# power_electronics2.net
KiCad netlist of a schematic drawn in EAGLE
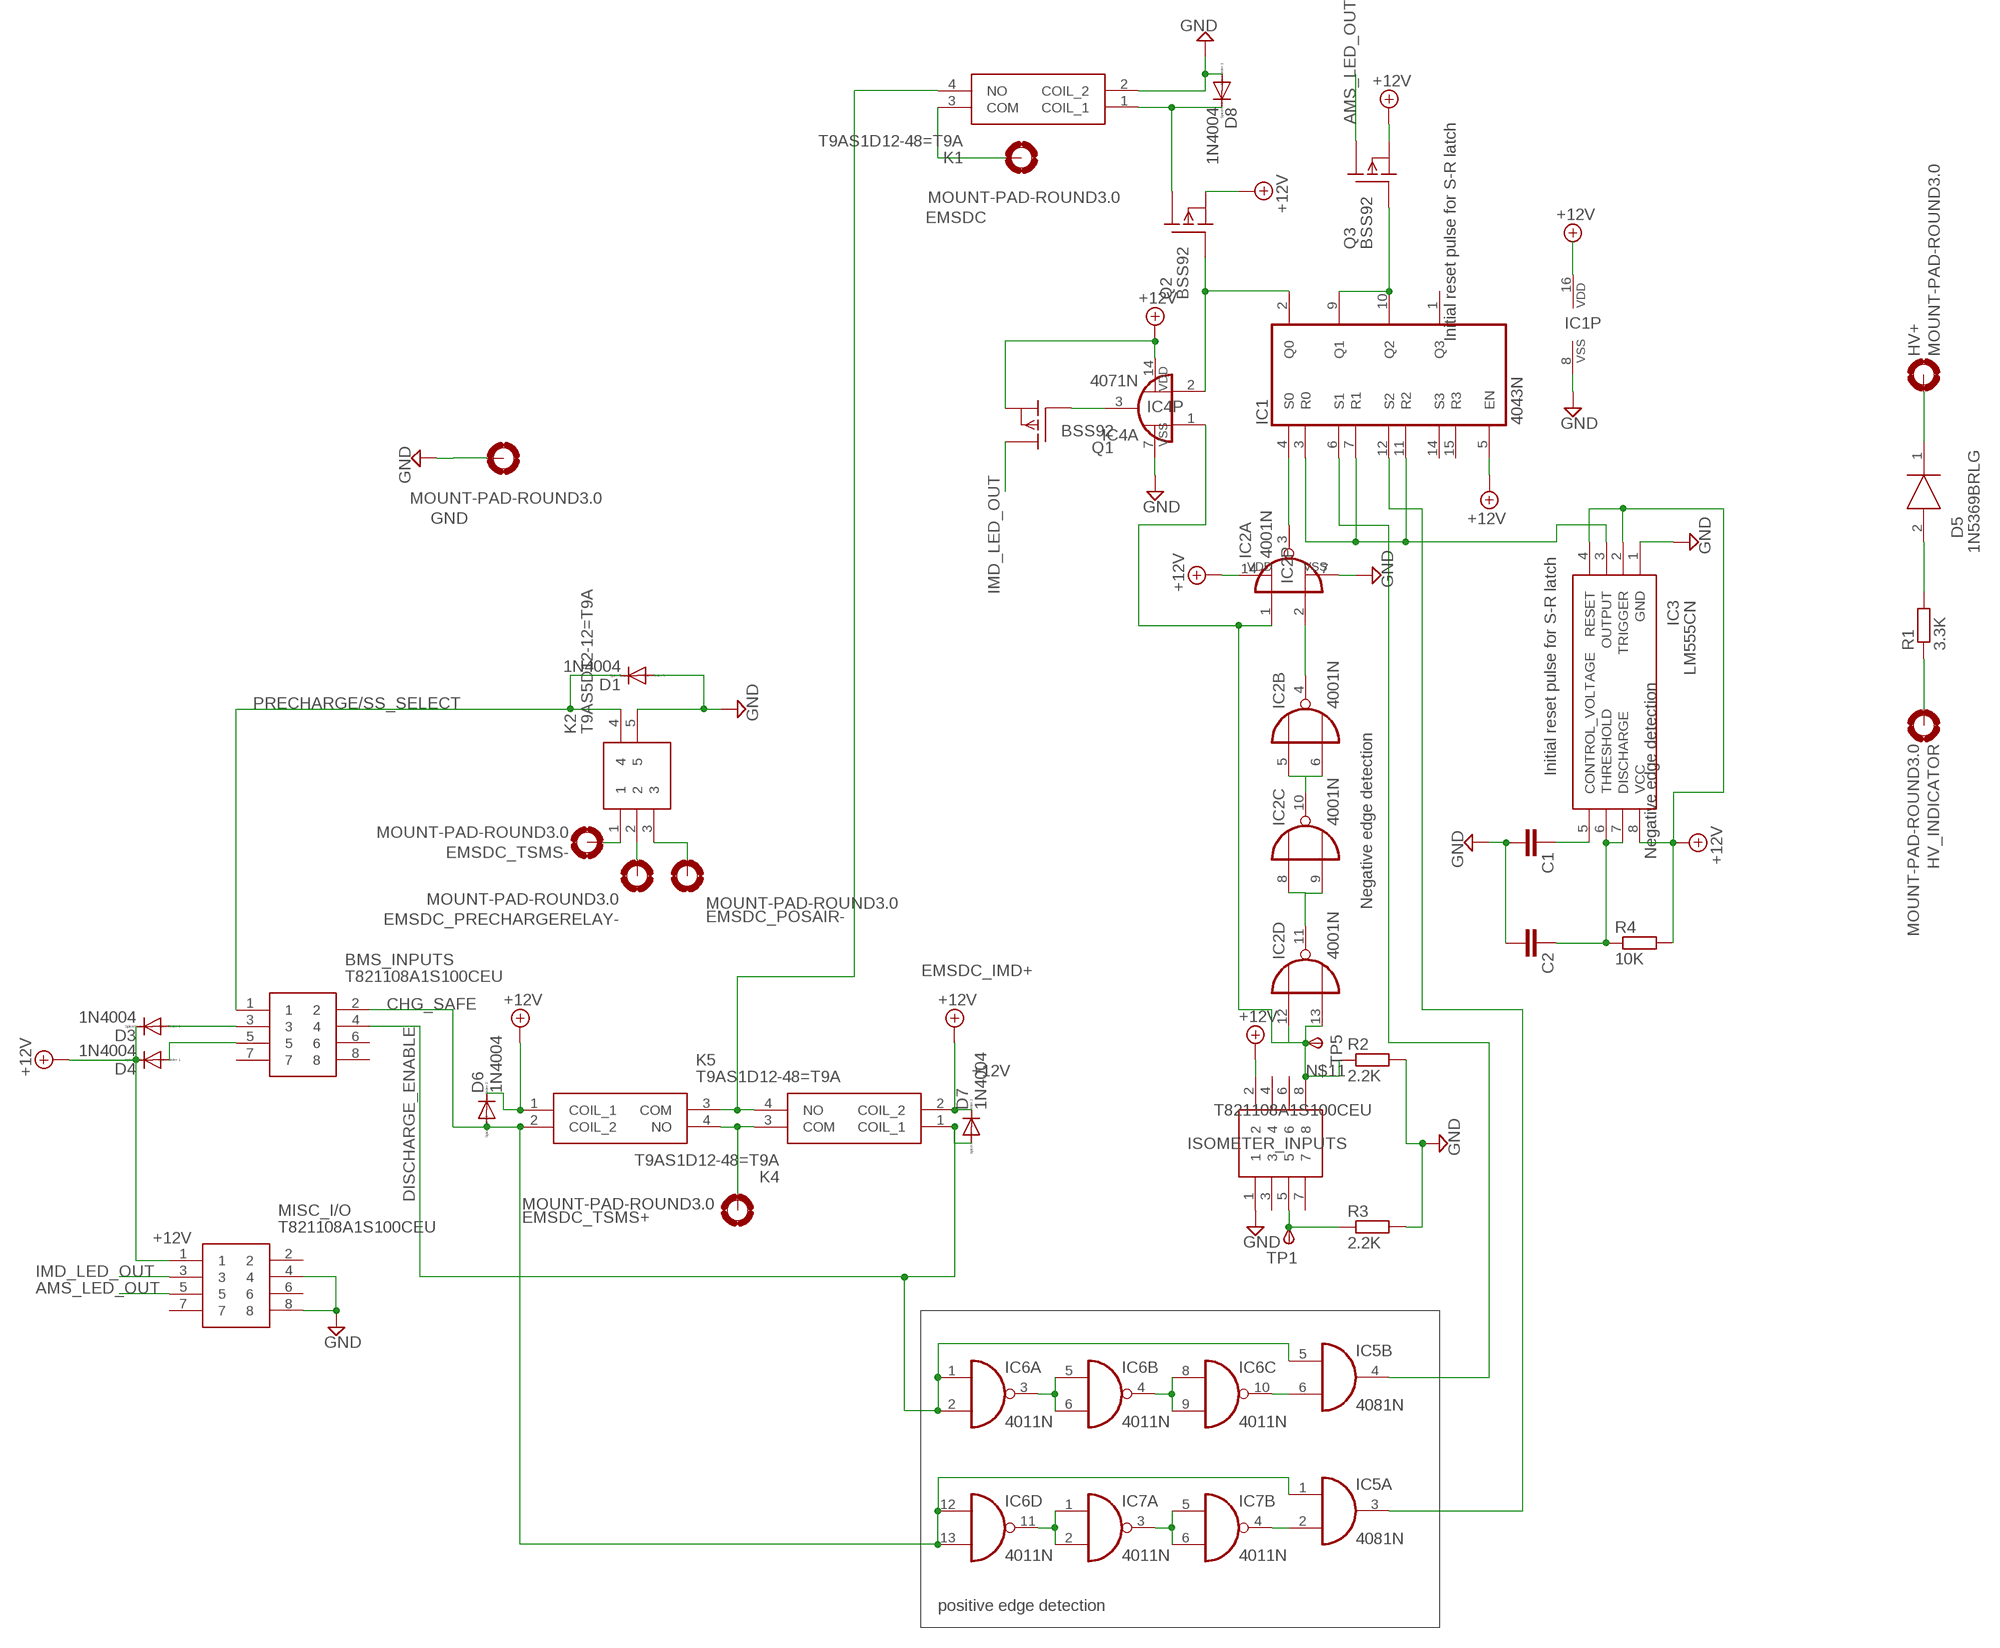
[diagram p0: schematic, sheet 1]

(export (version "E")
  (design (tool "Eeschema 10.0.6"))
  (components
    (comp (ref "BMS_INPUTS")
      (value "T821108A1S100CEU")
      (footprint "eagle-import:HDRV8W64P254_2X4_1778X895X915P")
      (fields (field (name "RS_PART_NUMBER") "8323569"))
      (libsource (lib "eagle-import") (part "T821108A1S100CEU"))
    )
    (comp (ref "C1")
      (value "C-EU050-024X044")
      (footprint "eagle-import:C050-024X044")
      (libsource (lib "eagle-import") (part "C-EU050-024X044"))
    )
    (comp (ref "C2")
      (value "C-EU050-024X044")
      (footprint "eagle-import:C050-024X044")
      (libsource (lib "eagle-import") (part "C-EU050-024X044"))
    )
    (comp (ref "D1")
      (value "1N4004")
      (footprint "eagle-import:DO41-10")
      (libsource (lib "eagle-import") (part "1N4004"))
    )
    (comp (ref "D3")
      (value "1N4004")
      (footprint "eagle-import:DO41-10")
      (libsource (lib "eagle-import") (part "1N4004"))
    )
    (comp (ref "D4")
      (value "1N4004")
      (footprint "eagle-import:DO41-10")
      (libsource (lib "eagle-import") (part "1N4004"))
    )
    (comp (ref "D5")
      (value "1N5369BRLG")
      (footprint "eagle-import:DIOAD2260W109L864D349")
      (fields (field (name "RS_PART_NUMBER") "6547678P"))
      (libsource (lib "eagle-import") (part "1N5369BRLG"))
    )
    (comp (ref "D6")
      (value "1N4004")
      (footprint "eagle-import:DO41-10")
      (libsource (lib "eagle-import") (part "1N4004"))
    )
    (comp (ref "D7")
      (value "1N4004")
      (footprint "eagle-import:DO41-10")
      (libsource (lib "eagle-import") (part "1N4004"))
    )
    (comp (ref "D8")
      (value "1N4004")
      (footprint "eagle-import:DO41-10")
      (libsource (lib "eagle-import") (part "1N4004"))
    )
    (comp (ref "EMSDC")
      (value "MOUNT-PAD-ROUND3.0")
      (footprint "eagle-import:3,0-PAD")
      (libsource (lib "eagle-import") (part "MOUNT-PAD-ROUND3.0"))
    )
    (comp (ref "EMSDC_POSAIR-")
      (value "MOUNT-PAD-ROUND3.0")
      (footprint "eagle-import:3,0-PAD")
      (libsource (lib "eagle-import") (part "MOUNT-PAD-ROUND3.0"))
    )
    (comp (ref "EMSDC_PRECHARGERELAY-")
      (value "MOUNT-PAD-ROUND3.0")
      (footprint "eagle-import:3,0-PAD")
      (libsource (lib "eagle-import") (part "MOUNT-PAD-ROUND3.0"))
    )
    (comp (ref "EMSDC_TSMS+")
      (value "MOUNT-PAD-ROUND3.0")
      (footprint "eagle-import:3,0-PAD")
      (libsource (lib "eagle-import") (part "MOUNT-PAD-ROUND3.0"))
    )
    (comp (ref "EMSDC_TSMS-")
      (value "MOUNT-PAD-ROUND3.0")
      (footprint "eagle-import:3,0-PAD")
      (libsource (lib "eagle-import") (part "MOUNT-PAD-ROUND3.0"))
    )
    (comp (ref "GND")
      (value "MOUNT-PAD-ROUND3.0")
      (footprint "eagle-import:3,0-PAD")
      (libsource (lib "eagle-import") (part "MOUNT-PAD-ROUND3.0"))
    )
    (comp (ref "HV+")
      (value "MOUNT-PAD-ROUND3.0")
      (footprint "eagle-import:3,0-PAD")
      (libsource (lib "eagle-import") (part "MOUNT-PAD-ROUND3.0"))
    )
    (comp (ref "HV_INDICATOR")
      (value "MOUNT-PAD-ROUND3.0")
      (footprint "eagle-import:3,0-PAD")
      (libsource (lib "eagle-import") (part "MOUNT-PAD-ROUND3.0"))
    )
    (comp (ref "IC1")
      (value "4043N")
      (footprint "eagle-import:DIL16")
      (libsource (lib "eagle-import") (part "4043N"))
    )
    (comp (ref "IC2")
      (value "4001N")
      (footprint "eagle-import:DIL14")
      (libsource (lib "eagle-import") (part "4001N"))
    )
    (comp (ref "IC3")
      (value "LM555CN")
      (footprint "eagle-import:DIP762W53P254L980H533Q8N")
      (fields (field (name "MOUSER_PART_NUMBER") "512-LM555CN"))
      (libsource (lib "eagle-import") (part "LM555CN"))
    )
    (comp (ref "IC4")
      (value "4071N")
      (footprint "eagle-import:DIL14")
      (libsource (lib "eagle-import") (part "4071N"))
    )
    (comp (ref "IC5")
      (value "4081N")
      (footprint "eagle-import:DIL14")
      (libsource (lib "eagle-import") (part "4081N"))
    )
    (comp (ref "IC6")
      (value "4011N")
      (footprint "eagle-import:DIL14")
      (libsource (lib "eagle-import") (part "4011N"))
    )
    (comp (ref "IC7")
      (value "4011N")
      (footprint "eagle-import:DIL14")
      (libsource (lib "eagle-import") (part "4011N"))
    )
    (comp (ref "ISOMETER_INPUTS")
      (value "T821108A1S100CEU")
      (footprint "eagle-import:HDRV8W64P254_2X4_1778X895X915P")
      (fields (field (name "RS_PART_NUMBER") "8323569"))
      (libsource (lib "eagle-import") (part "T821108A1S100CEU"))
    )
    (comp (ref "K1")
      (value "T9AS1D12-48=T9A")
      (footprint "eagle-import:T9AS1D1248T9A")
      (fields (field (name "RS_PART_NUMBER") "6802534P"))
      (libsource (lib "eagle-import") (part "T9AS1D12-48=T9A"))
    )
    (comp (ref "K2")
      (value "T9AS5D12-12=T9A")
      (footprint "eagle-import:T9AS1D12")
      (fields (field (name "RS_PART_NUMBER") "6802528"))
      (libsource (lib "eagle-import") (part "T9AS5D12-12=T9A"))
    )
    (comp (ref "K4")
      (value "T9AS1D12-48=T9A")
      (footprint "eagle-import:T9AS1D1248T9A")
      (fields (field (name "RS_PART_NUMBER") "6802534P"))
      (libsource (lib "eagle-import") (part "T9AS1D12-48=T9A"))
    )
    (comp (ref "K5")
      (value "T9AS1D12-48=T9A")
      (footprint "eagle-import:T9AS1D1248T9A")
      (fields (field (name "RS_PART_NUMBER") "6802534P"))
      (libsource (lib "eagle-import") (part "T9AS1D12-48=T9A"))
    )
    (comp (ref "MISC_I/O")
      (value "T821108A1S100CEU")
      (footprint "eagle-import:HDRV8W64P254_2X4_1778X895X915P")
      (fields (field (name "RS_PART_NUMBER") "8323569"))
      (libsource (lib "eagle-import") (part "T821108A1S100CEU"))
    )
    (comp (ref "Q1")
      (value "BSS92")
      (footprint "eagle-import:TO92")
      (libsource (lib "eagle-import") (part "BSS92"))
    )
    (comp (ref "Q2")
      (value "BSS92")
      (footprint "eagle-import:TO92")
      (libsource (lib "eagle-import") (part "BSS92"))
    )
    (comp (ref "Q3")
      (value "BSS92")
      (footprint "eagle-import:TO92")
      (libsource (lib "eagle-import") (part "BSS92"))
    )
    (comp (ref "R1")
      (value "3.3K")
      (footprint "eagle-import:0207_15")
      (libsource (lib "eagle-import") (part "R-EU_0207/15"))
    )
    (comp (ref "R2")
      (value "2.2K")
      (footprint "eagle-import:0207_12")
      (libsource (lib "eagle-import") (part "R-EU_0207/12"))
    )
    (comp (ref "R3")
      (value "2.2K")
      (footprint "eagle-import:0207_12")
      (libsource (lib "eagle-import") (part "R-EU_0207/12"))
    )
    (comp (ref "R4")
      (value "10K")
      (footprint "eagle-import:0207_15")
      (libsource (lib "eagle-import") (part "R-EU_0207/15"))
    )
    (comp (ref "TP1")
      (value "TPSPAD1-17")
      (footprint "eagle-import:P1-17")
      (libsource (lib "eagle-import") (part "TPSPAD1-17"))
    )
    (comp (ref "TP5")
      (value "TPSPAD1-17")
      (footprint "eagle-import:P1-17")
      (libsource (lib "eagle-import") (part "TPSPAD1-17"))
    )
  )
  (nets
    (net (code "1") (name "+12V") (class "Default")
      (node (ref "D3") (pin "C") (pinfunction "C_C") (pintype "passive"))
      (node (ref "D4") (pin "C") (pinfunction "C_C") (pintype "passive"))
      (node (ref "D6") (pin "C") (pinfunction "C_C") (pintype "passive"))
      (node (ref "D7") (pin "C") (pinfunction "C_C") (pintype "passive"))
      (node (ref "IC1") (pin "16") (pinfunction "VDD_16") (pintype "power_in"))
      (node (ref "IC1") (pin "5") (pinfunction "EN_5") (pintype "input"))
      (node (ref "IC2") (pin "14") (pinfunction "VDD_14") (pintype "power_in"))
      (node (ref "IC3") (pin "2") (pinfunction "TRIGGER_2") (pintype "bidirectional"))
      (node (ref "IC3") (pin "4") (pinfunction "RESET_4") (pintype "bidirectional"))
      (node (ref "IC3") (pin "8") (pinfunction "VCC_8") (pintype "bidirectional"))
      (node (ref "IC4") (pin "14") (pinfunction "VDD_14") (pintype "power_in"))
      (node (ref "ISOMETER_INPUTS") (pin "2") (pinfunction "2_2") (pintype "bidirectional"))
      (node (ref "K4") (pin "2") (pinfunction "COIL_2_2") (pintype "bidirectional"))
      (node (ref "K5") (pin "1") (pinfunction "COIL_1_1") (pintype "bidirectional"))
      (node (ref "MISC_I/O") (pin "1") (pinfunction "1_1") (pintype "bidirectional"))
      (node (ref "Q1") (pin "3") (pinfunction "S_3") (pintype "passive"))
      (node (ref "Q2") (pin "3") (pinfunction "S_3") (pintype "passive"))
      (node (ref "Q3") (pin "3") (pinfunction "S_3") (pintype "passive"))
      (node (ref "R4") (pin "2") (pinfunction "2_2") (pintype "passive"))
    )
    (net (code "2") (name "/AMS_LED_OUT") (class "Default")
      (node (ref "MISC_I/O") (pin "5") (pinfunction "5_5") (pintype "bidirectional"))
      (node (ref "Q3") (pin "2") (pinfunction "D_2") (pintype "passive"))
    )
    (net (code "3") (name "/CHG_SAFE") (class "Default")
      (node (ref "BMS_INPUTS") (pin "2") (pinfunction "2_2") (pintype "bidirectional"))
      (node (ref "D6") (pin "A") (pinfunction "A_A") (pintype "passive"))
      (node (ref "IC5") (pin "1") (pinfunction "I0_1") (pintype "input"))
      (node (ref "IC6") (pin "12") (pinfunction "I0_12") (pintype "input"))
      (node (ref "IC6") (pin "13") (pinfunction "I1_13") (pintype "input"))
      (node (ref "K5") (pin "2") (pinfunction "COIL_2_2") (pintype "bidirectional"))
    )
    (net (code "4") (name "/DISCHARGE_ENABLE") (class "Default")
      (node (ref "BMS_INPUTS") (pin "4") (pinfunction "4_4") (pintype "bidirectional"))
      (node (ref "D7") (pin "A") (pinfunction "A_A") (pintype "passive"))
      (node (ref "IC5") (pin "5") (pinfunction "I0_5") (pintype "input"))
      (node (ref "IC6") (pin "1") (pinfunction "I0_1") (pintype "input"))
      (node (ref "IC6") (pin "2") (pinfunction "I1_2") (pintype "input"))
      (node (ref "K4") (pin "1") (pinfunction "COIL_1_1") (pintype "bidirectional"))
    )
    (net (code "5") (name "/EMSDC_IMD+") (class "Default")
      (node (ref "K1") (pin "4") (pinfunction "NO_4") (pintype "bidirectional"))
      (node (ref "K4") (pin "4") (pinfunction "NO_4") (pintype "bidirectional"))
      (node (ref "K5") (pin "3") (pinfunction "COM_3") (pintype "bidirectional"))
    )
    (net (code "6") (name "/IMD_LED_OUT") (class "Default")
      (node (ref "MISC_I/O") (pin "3") (pinfunction "3_3") (pintype "bidirectional"))
      (node (ref "Q1") (pin "2") (pinfunction "D_2") (pintype "passive"))
    )
    (net (code "7") (name "/N$11") (class "Default")
      (node (ref "IC2") (pin "1") (pinfunction "I0_1") (pintype "input"))
      (node (ref "IC2") (pin "12") (pinfunction "I0_12") (pintype "input"))
      (node (ref "IC2") (pin "13") (pinfunction "I1_13") (pintype "input"))
      (node (ref "IC4") (pin "1") (pinfunction "I0_1") (pintype "input"))
      (node (ref "ISOMETER_INPUTS") (pin "8") (pinfunction "8_8") (pintype "bidirectional"))
      (node (ref "R2") (pin "1") (pinfunction "1_1") (pintype "passive"))
      (node (ref "TP5") (pin "TP") (pinfunction "PP_TP") (pintype "input"))
    )
    (net (code "8") (name "/PRECHARGE{slash}SS_SELECT") (class "Default")
      (node (ref "BMS_INPUTS") (pin "1") (pinfunction "1_1") (pintype "bidirectional"))
      (node (ref "D1") (pin "C") (pinfunction "C_C") (pintype "passive"))
      (node (ref "K2") (pin "4") (pinfunction "4_4") (pintype "bidirectional"))
    )
    (net (code "9") (name "GND") (class "Default")
      (node (ref "C1") (pin "2") (pinfunction "2_2") (pintype "passive"))
      (node (ref "C2") (pin "2") (pinfunction "2_2") (pintype "passive"))
      (node (ref "D1") (pin "A") (pinfunction "A_A") (pintype "passive"))
      (node (ref "D8") (pin "A") (pinfunction "A_A") (pintype "passive"))
      (node (ref "GND") (pin "B3,0") (pinfunction "MOUNT_B3,0") (pintype "passive"))
      (node (ref "IC1") (pin "8") (pinfunction "VSS_8") (pintype "power_in"))
      (node (ref "IC2") (pin "7") (pinfunction "VSS_7") (pintype "power_in"))
      (node (ref "IC3") (pin "1") (pinfunction "GND_1") (pintype "bidirectional"))
      (node (ref "IC4") (pin "7") (pinfunction "VSS_7") (pintype "power_in"))
      (node (ref "ISOMETER_INPUTS") (pin "1") (pinfunction "1_1") (pintype "bidirectional"))
      (node (ref "K1") (pin "2") (pinfunction "COIL_2_2") (pintype "bidirectional"))
      (node (ref "K2") (pin "5") (pinfunction "5_5") (pintype "bidirectional"))
      (node (ref "MISC_I/O") (pin "4") (pinfunction "4_4") (pintype "bidirectional"))
      (node (ref "MISC_I/O") (pin "8") (pinfunction "8_8") (pintype "bidirectional"))
      (node (ref "R2") (pin "2") (pinfunction "2_2") (pintype "passive"))
      (node (ref "R3") (pin "2") (pinfunction "2_2") (pintype "passive"))
    )
    (net (code "10") (name "Net-(BMS_INPUTS-Pad3)") (class "Default")
      (node (ref "BMS_INPUTS") (pin "3") (pinfunction "3_3") (pintype "bidirectional"))
      (node (ref "D3") (pin "A") (pinfunction "A_A") (pintype "passive"))
    )
    (net (code "11") (name "Net-(BMS_INPUTS-Pad5)") (class "Default")
      (node (ref "BMS_INPUTS") (pin "5") (pinfunction "5_5") (pintype "bidirectional"))
      (node (ref "D4") (pin "A") (pinfunction "A_A") (pintype "passive"))
    )
    (net (code "12") (name "Net-(D5-A)") (class "Default")
      (node (ref "D5") (pin "2") (pinfunction "A_2") (pintype "bidirectional"))
      (node (ref "R1") (pin "2") (pinfunction "2_2") (pintype "passive"))
    )
    (net (code "13") (name "Net-(D5-K)") (class "Default")
      (node (ref "D5") (pin "1") (pinfunction "K_1") (pintype "bidirectional"))
      (node (ref "HV+") (pin "B3,0") (pinfunction "MOUNT_B3,0") (pintype "passive"))
    )
    (net (code "14") (name "Net-(EMSDC-MOUNT)") (class "Default")
      (node (ref "EMSDC") (pin "B3,0") (pinfunction "MOUNT_B3,0") (pintype "passive"))
      (node (ref "K1") (pin "3") (pinfunction "COM_3") (pintype "bidirectional"))
    )
    (net (code "15") (name "Net-(EMSDC_POSAIR--MOUNT)") (class "Default")
      (node (ref "EMSDC_POSAIR-") (pin "B3,0") (pinfunction "MOUNT_B3,0") (pintype "passive"))
      (node (ref "K2") (pin "3") (pinfunction "3_3") (pintype "bidirectional"))
    )
    (net (code "16") (name "Net-(EMSDC_PRECHARGERELAY--MOUNT)") (class "Default")
      (node (ref "EMSDC_PRECHARGERELAY-") (pin "B3,0") (pinfunction "MOUNT_B3,0") (pintype "passive"))
      (node (ref "K2") (pin "2") (pinfunction "2_2") (pintype "bidirectional"))
    )
    (net (code "17") (name "Net-(EMSDC_TSMS+-MOUNT)") (class "Default")
      (node (ref "EMSDC_TSMS+") (pin "B3,0") (pinfunction "MOUNT_B3,0") (pintype "passive"))
      (node (ref "K4") (pin "3") (pinfunction "COM_3") (pintype "bidirectional"))
      (node (ref "K5") (pin "4") (pinfunction "NO_4") (pintype "bidirectional"))
    )
    (net (code "18") (name "Net-(EMSDC_TSMS--MOUNT)") (class "Default")
      (node (ref "EMSDC_TSMS-") (pin "B3,0") (pinfunction "MOUNT_B3,0") (pintype "passive"))
      (node (ref "K2") (pin "1") (pinfunction "1_1") (pintype "bidirectional"))
    )
    (net (code "19") (name "Net-(HV_INDICATOR-MOUNT)") (class "Default")
      (node (ref "HV_INDICATOR") (pin "B3,0") (pinfunction "MOUNT_B3,0") (pintype "passive"))
      (node (ref "R1") (pin "1") (pinfunction "1_1") (pintype "passive"))
    )
    (net (code "20") (name "Net-(IC1A-Q0)") (class "Default")
      (node (ref "IC1") (pin "2") (pinfunction "Q0_2") (pintype "output"))
      (node (ref "IC4") (pin "2") (pinfunction "I1_2") (pintype "input"))
      (node (ref "Q2") (pin "1") (pinfunction "G_1") (pintype "passive"))
    )
    (net (code "21") (name "Net-(IC1A-Q1)") (class "Default")
      (node (ref "IC1") (pin "10") (pinfunction "Q2_10") (pintype "output"))
      (node (ref "IC1") (pin "9") (pinfunction "Q1_9") (pintype "output"))
      (node (ref "Q3") (pin "1") (pinfunction "G_1") (pintype "passive"))
    )
    (net (code "22") (name "Net-(IC1A-R0)") (class "Default")
      (node (ref "IC1") (pin "11") (pinfunction "R2_11") (pintype "input"))
      (node (ref "IC1") (pin "3") (pinfunction "R0_3") (pintype "input"))
      (node (ref "IC1") (pin "7") (pinfunction "R1_7") (pintype "input"))
      (node (ref "IC3") (pin "3") (pinfunction "OUTPUT_3") (pintype "bidirectional"))
    )
    (net (code "23") (name "Net-(IC1A-S0)") (class "Default")
      (node (ref "IC1") (pin "4") (pinfunction "S0_4") (pintype "input"))
      (node (ref "IC2") (pin "3") (pinfunction "O_3") (pintype "output"))
    )
    (net (code "24") (name "Net-(IC1A-S1)") (class "Default")
      (node (ref "IC1") (pin "6") (pinfunction "S1_6") (pintype "input"))
      (node (ref "IC5") (pin "4") (pinfunction "O_4") (pintype "output"))
    )
    (net (code "25") (name "Net-(IC1A-S2)") (class "Default")
      (node (ref "IC1") (pin "12") (pinfunction "S2_12") (pintype "input"))
      (node (ref "IC5") (pin "3") (pinfunction "O_3") (pintype "output"))
    )
    (net (code "26") (name "Net-(IC2A-I1)") (class "Default")
      (node (ref "IC2") (pin "2") (pinfunction "I1_2") (pintype "input"))
      (node (ref "IC2") (pin "4") (pinfunction "O_4") (pintype "output"))
    )
    (net (code "27") (name "Net-(IC2B-I0)") (class "Default")
      (node (ref "IC2") (pin "10") (pinfunction "O_10") (pintype "output"))
      (node (ref "IC2") (pin "5") (pinfunction "I0_5") (pintype "input"))
      (node (ref "IC2") (pin "6") (pinfunction "I1_6") (pintype "input"))
    )
    (net (code "28") (name "Net-(IC2C-I0)") (class "Default")
      (node (ref "IC2") (pin "11") (pinfunction "O_11") (pintype "output"))
      (node (ref "IC2") (pin "8") (pinfunction "I0_8") (pintype "input"))
      (node (ref "IC2") (pin "9") (pinfunction "I1_9") (pintype "input"))
    )
    (net (code "29") (name "Net-(IC3-CONTROL_VOLTAGE)") (class "Default")
      (node (ref "C1") (pin "1") (pinfunction "1_1") (pintype "passive"))
      (node (ref "IC3") (pin "5") (pinfunction "CONTROL_VOLTAGE_5") (pintype "bidirectional"))
    )
    (net (code "30") (name "Net-(IC3-DISCHARGE)") (class "Default")
      (node (ref "C2") (pin "1") (pinfunction "1_1") (pintype "passive"))
      (node (ref "IC3") (pin "6") (pinfunction "THRESHOLD_6") (pintype "bidirectional"))
      (node (ref "IC3") (pin "7") (pinfunction "DISCHARGE_7") (pintype "bidirectional"))
      (node (ref "R4") (pin "1") (pinfunction "1_1") (pintype "passive"))
    )
    (net (code "31") (name "Net-(IC4A-O)") (class "Default")
      (node (ref "IC4") (pin "3") (pinfunction "O_3") (pintype "output"))
      (node (ref "Q1") (pin "1") (pinfunction "G_1") (pintype "passive"))
    )
    (net (code "32") (name "Net-(IC5A-I1)") (class "Default")
      (node (ref "IC5") (pin "2") (pinfunction "I1_2") (pintype "input"))
      (node (ref "IC7") (pin "4") (pinfunction "O_4") (pintype "output"))
    )
    (net (code "33") (name "Net-(IC5B-I1)") (class "Default")
      (node (ref "IC5") (pin "6") (pinfunction "I1_6") (pintype "input"))
      (node (ref "IC6") (pin "10") (pinfunction "O_10") (pintype "output"))
    )
    (net (code "34") (name "Net-(IC6A-O)") (class "Default")
      (node (ref "IC6") (pin "3") (pinfunction "O_3") (pintype "output"))
      (node (ref "IC6") (pin "5") (pinfunction "I0_5") (pintype "input"))
      (node (ref "IC6") (pin "6") (pinfunction "I1_6") (pintype "input"))
    )
    (net (code "35") (name "Net-(IC6B-O)") (class "Default")
      (node (ref "IC6") (pin "4") (pinfunction "O_4") (pintype "output"))
      (node (ref "IC6") (pin "8") (pinfunction "I0_8") (pintype "input"))
      (node (ref "IC6") (pin "9") (pinfunction "I1_9") (pintype "input"))
    )
    (net (code "36") (name "Net-(IC6D-O)") (class "Default")
      (node (ref "IC6") (pin "11") (pinfunction "O_11") (pintype "output"))
      (node (ref "IC7") (pin "1") (pinfunction "I0_1") (pintype "input"))
      (node (ref "IC7") (pin "2") (pinfunction "I1_2") (pintype "input"))
    )
    (net (code "37") (name "Net-(IC7A-O)") (class "Default")
      (node (ref "IC7") (pin "3") (pinfunction "O_3") (pintype "output"))
      (node (ref "IC7") (pin "5") (pinfunction "I0_5") (pintype "input"))
      (node (ref "IC7") (pin "6") (pinfunction "I1_6") (pintype "input"))
    )
    (net (code "38") (name "Net-(K1-COIL_1)") (class "Default")
      (node (ref "D8") (pin "C") (pinfunction "C_C") (pintype "passive"))
      (node (ref "K1") (pin "1") (pinfunction "COIL_1_1") (pintype "bidirectional"))
      (node (ref "Q2") (pin "2") (pinfunction "D_2") (pintype "passive"))
    )
    (net (code "39") (name "Net-(TP1-PP)") (class "Default")
      (node (ref "ISOMETER_INPUTS") (pin "5") (pinfunction "5_5") (pintype "bidirectional"))
      (node (ref "R3") (pin "1") (pinfunction "1_1") (pintype "passive"))
      (node (ref "TP1") (pin "TP") (pinfunction "PP_TP") (pintype "input"))
    )
    (net (code "40") (name "unconnected-(BMS_INPUTS-Pad6)") (class "Default")
      (node (ref "BMS_INPUTS") (pin "6") (pinfunction "6_6") (pintype "bidirectional"))
    )
    (net (code "41") (name "unconnected-(BMS_INPUTS-Pad7)") (class "Default")
      (node (ref "BMS_INPUTS") (pin "7") (pinfunction "7_7") (pintype "bidirectional"))
    )
    (net (code "42") (name "unconnected-(BMS_INPUTS-Pad8)") (class "Default")
      (node (ref "BMS_INPUTS") (pin "8") (pinfunction "8_8") (pintype "bidirectional"))
    )
    (net (code "43") (name "unconnected-(IC1A-Q3-Pad1)") (class "Default")
      (node (ref "IC1") (pin "1") (pinfunction "Q3_1") (pintype "output"))
    )
    (net (code "44") (name "unconnected-(IC1A-R3-Pad15)") (class "Default")
      (node (ref "IC1") (pin "15") (pinfunction "R3_15") (pintype "input"))
    )
    (net (code "45") (name "unconnected-(IC1A-S3-Pad14)") (class "Default")
      (node (ref "IC1") (pin "14") (pinfunction "S3_14") (pintype "input"))
    )
    (net (code "46") (name "unconnected-(ISOMETER_INPUTS-Pad3)") (class "Default")
      (node (ref "ISOMETER_INPUTS") (pin "3") (pinfunction "3_3") (pintype "bidirectional"))
    )
    (net (code "47") (name "unconnected-(ISOMETER_INPUTS-Pad4)") (class "Default")
      (node (ref "ISOMETER_INPUTS") (pin "4") (pinfunction "4_4") (pintype "bidirectional"))
    )
    (net (code "48") (name "unconnected-(ISOMETER_INPUTS-Pad6)") (class "Default")
      (node (ref "ISOMETER_INPUTS") (pin "6") (pinfunction "6_6") (pintype "bidirectional"))
    )
    (net (code "49") (name "unconnected-(ISOMETER_INPUTS-Pad7)") (class "Default")
      (node (ref "ISOMETER_INPUTS") (pin "7") (pinfunction "7_7") (pintype "bidirectional"))
    )
    (net (code "50") (name "unconnected-(MISC_I/O-Pad2)") (class "Default")
      (node (ref "MISC_I/O") (pin "2") (pinfunction "2_2") (pintype "bidirectional"))
    )
    (net (code "51") (name "unconnected-(MISC_I/O-Pad6)") (class "Default")
      (node (ref "MISC_I/O") (pin "6") (pinfunction "6_6") (pintype "bidirectional"))
    )
    (net (code "52") (name "unconnected-(MISC_I/O-Pad7)") (class "Default")
      (node (ref "MISC_I/O") (pin "7") (pinfunction "7_7") (pintype "bidirectional"))
    )
  )
)
